# ADF4351.net
KiCad netlist of a schematic drawn in EAGLE
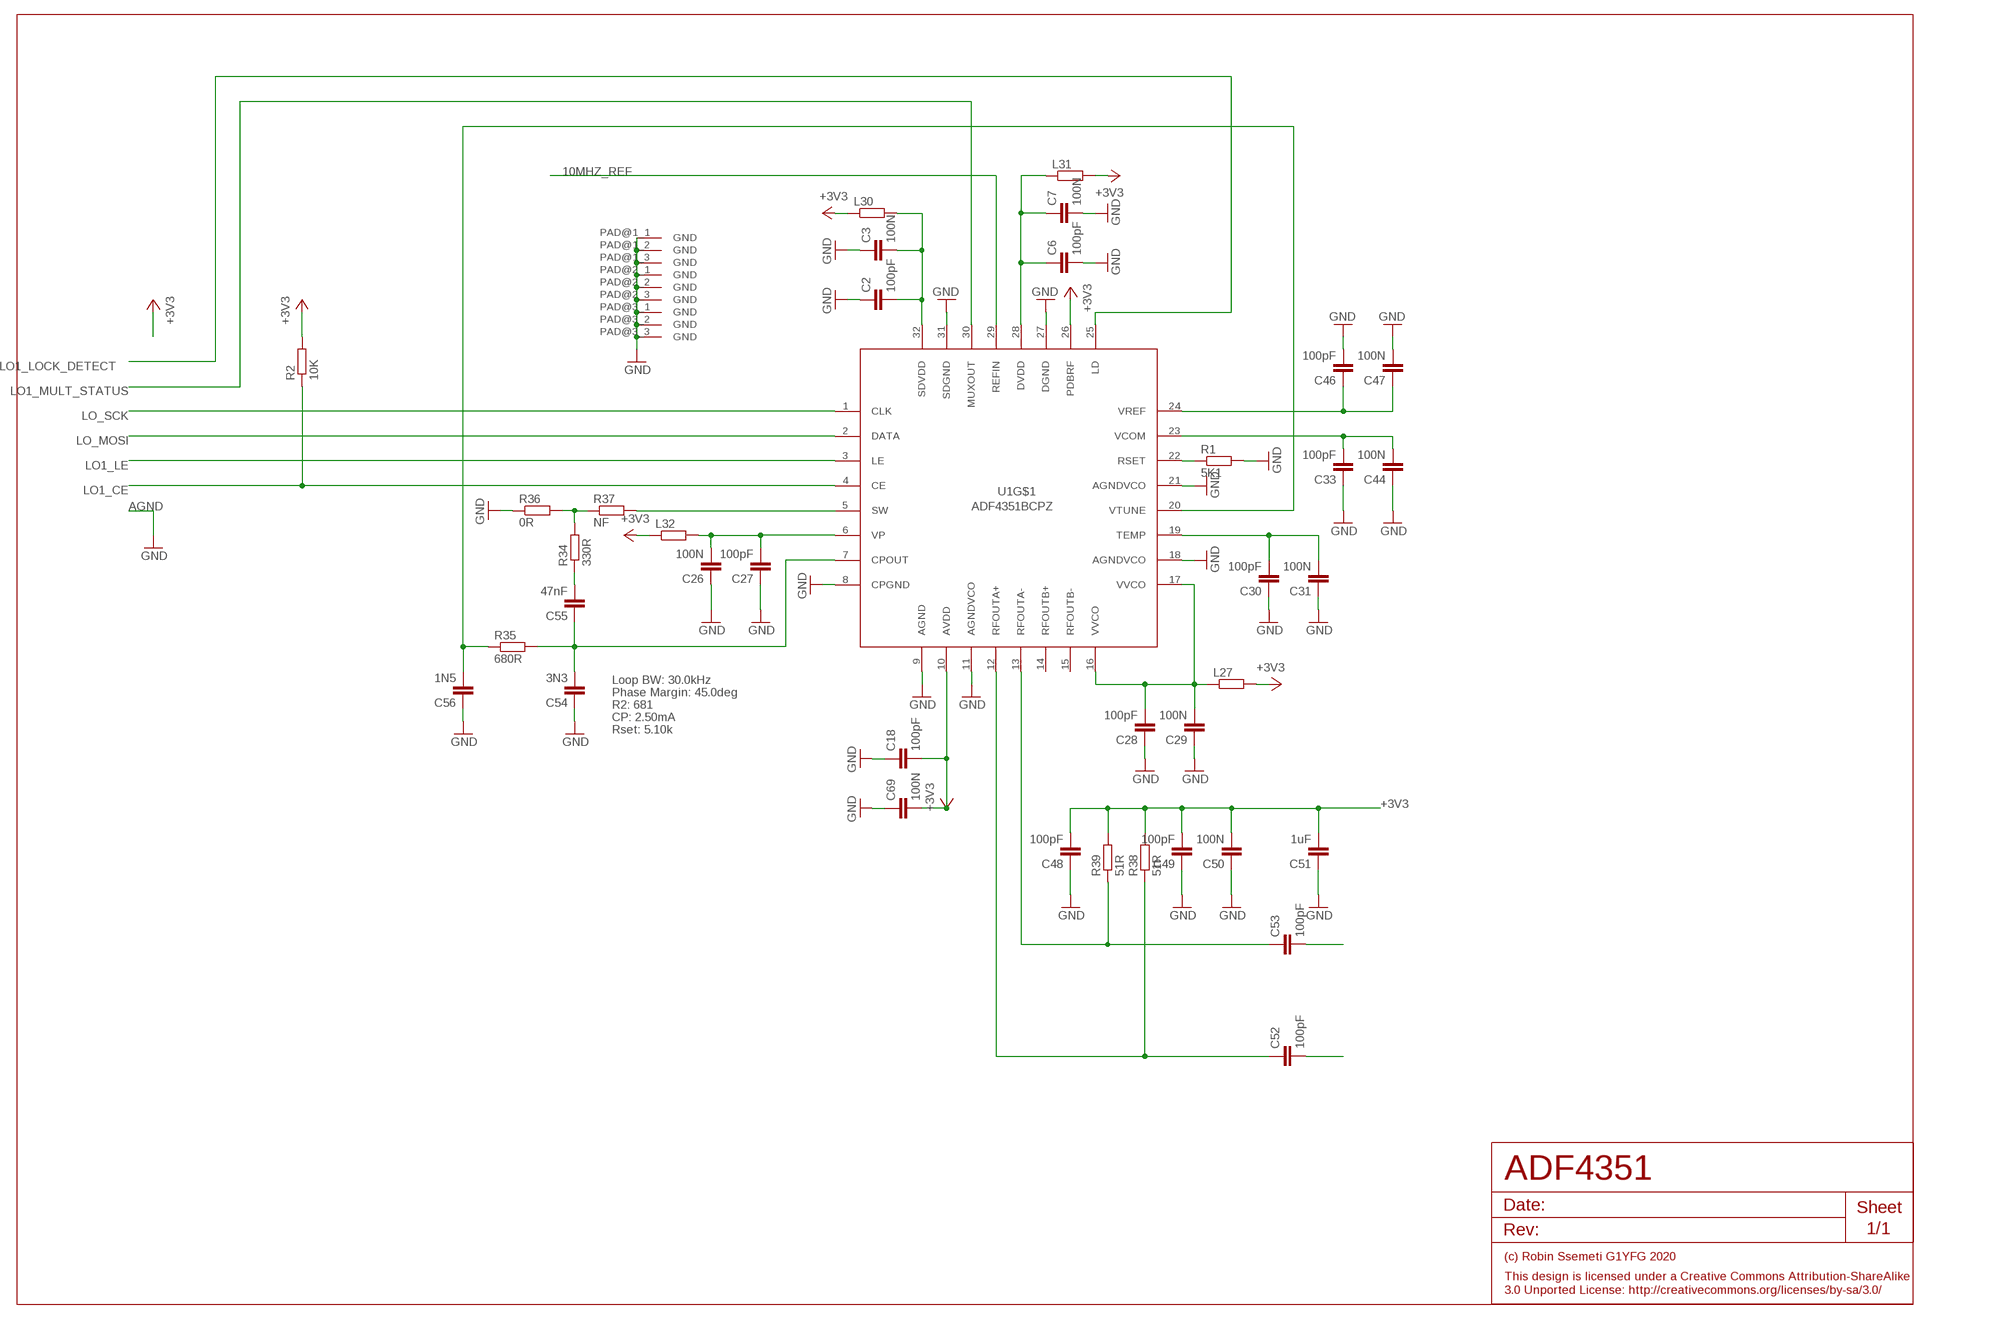
[diagram p0: schematic, sheet 1]

(export (version "E")
  (design (tool "Eeschema 10.0.6"))
  (components
    (comp (ref "C2")
      (value "100pF")
      (footprint "eagle-import:C0603")
      (libsource (lib "eagle-import") (part "C-EUC0603"))
    )
    (comp (ref "C3")
      (value "100N")
      (footprint "eagle-import:C0603")
      (libsource (lib "eagle-import") (part "C-EUC0603"))
    )
    (comp (ref "C6")
      (value "100pF")
      (footprint "eagle-import:C0603")
      (libsource (lib "eagle-import") (part "C-EUC0603"))
    )
    (comp (ref "C7")
      (value "100N")
      (footprint "eagle-import:C0603")
      (libsource (lib "eagle-import") (part "C-EUC0603"))
    )
    (comp (ref "C18")
      (value "100pF")
      (footprint "eagle-import:C0603")
      (libsource (lib "eagle-import") (part "C-EUC0603"))
    )
    (comp (ref "C26")
      (value "100N")
      (footprint "eagle-import:C0603")
      (libsource (lib "eagle-import") (part "C-EUC0603"))
    )
    (comp (ref "C27")
      (value "100pF")
      (footprint "eagle-import:C0603")
      (libsource (lib "eagle-import") (part "C-EUC0603"))
    )
    (comp (ref "C28")
      (value "100pF")
      (footprint "eagle-import:C0603")
      (libsource (lib "eagle-import") (part "C-EUC0603"))
    )
    (comp (ref "C29")
      (value "100N")
      (footprint "eagle-import:C0603")
      (libsource (lib "eagle-import") (part "C-EUC0603"))
    )
    (comp (ref "C30")
      (value "100pF")
      (footprint "eagle-import:C0603")
      (libsource (lib "eagle-import") (part "C-EUC0603"))
    )
    (comp (ref "C31")
      (value "100N")
      (footprint "eagle-import:C0603")
      (libsource (lib "eagle-import") (part "C-EUC0603"))
    )
    (comp (ref "C33")
      (value "100pF")
      (footprint "eagle-import:C0603")
      (libsource (lib "eagle-import") (part "C-EUC0603"))
    )
    (comp (ref "C44")
      (value "100N")
      (footprint "eagle-import:C0603")
      (libsource (lib "eagle-import") (part "C-EUC0603"))
    )
    (comp (ref "C46")
      (value "100pF")
      (footprint "eagle-import:C0603")
      (libsource (lib "eagle-import") (part "C-EUC0603"))
    )
    (comp (ref "C47")
      (value "100N")
      (footprint "eagle-import:C0603")
      (libsource (lib "eagle-import") (part "C-EUC0603"))
    )
    (comp (ref "C48")
      (value "100pF")
      (footprint "eagle-import:C0603")
      (libsource (lib "eagle-import") (part "C-EUC0603"))
    )
    (comp (ref "C49")
      (value "100pF")
      (footprint "eagle-import:C0603")
      (libsource (lib "eagle-import") (part "C-EUC0603"))
    )
    (comp (ref "C50")
      (value "100N")
      (footprint "eagle-import:C0603")
      (libsource (lib "eagle-import") (part "C-EUC0603"))
    )
    (comp (ref "C51")
      (value "1uF")
      (footprint "eagle-import:C0603")
      (libsource (lib "eagle-import") (part "C-EUC0603"))
    )
    (comp (ref "C52")
      (value "100pF")
      (footprint "eagle-import:C0603")
      (libsource (lib "eagle-import") (part "C-EUC0603"))
    )
    (comp (ref "C53")
      (value "100pF")
      (footprint "eagle-import:C0603")
      (libsource (lib "eagle-import") (part "C-EUC0603"))
    )
    (comp (ref "C54")
      (value "3N3")
      (footprint "eagle-import:C0603")
      (libsource (lib "eagle-import") (part "C-EUC0603"))
    )
    (comp (ref "C55")
      (value "47nF")
      (footprint "eagle-import:C0603")
      (libsource (lib "eagle-import") (part "C-EUC0603"))
    )
    (comp (ref "C56")
      (value "1N5")
      (footprint "eagle-import:C0603")
      (libsource (lib "eagle-import") (part "C-EUC0603"))
    )
    (comp (ref "C69")
      (value "100N")
      (footprint "eagle-import:C0603")
      (libsource (lib "eagle-import") (part "C-EUC0603"))
    )
    (comp (ref "L27")
      (value "R-EU_R0603")
      (footprint "eagle-import:R0603")
      (libsource (lib "eagle-import") (part "R-EU_R0603"))
    )
    (comp (ref "L30")
      (value "R-EU_R0603")
      (footprint "eagle-import:R0603")
      (libsource (lib "eagle-import") (part "R-EU_R0603"))
    )
    (comp (ref "L31")
      (value "R-EU_R0603")
      (footprint "eagle-import:R0603")
      (libsource (lib "eagle-import") (part "R-EU_R0603"))
    )
    (comp (ref "L32")
      (value "R-EU_R0603")
      (footprint "eagle-import:R0603")
      (libsource (lib "eagle-import") (part "R-EU_R0603"))
    )
    (comp (ref "R1")
      (value "5K1")
      (footprint "eagle-import:R0603")
      (libsource (lib "eagle-import") (part "R-EU_R0603"))
    )
    (comp (ref "R2")
      (value "10K")
      (footprint "eagle-import:R0603")
      (libsource (lib "eagle-import") (part "resistor_R-EU_R0603"))
    )
    (comp (ref "R34")
      (value "330R")
      (footprint "eagle-import:R0603")
      (libsource (lib "eagle-import") (part "R-EU_R0603"))
    )
    (comp (ref "R35")
      (value "680R")
      (footprint "eagle-import:R0603")
      (libsource (lib "eagle-import") (part "resistor_R-EU_R0603"))
    )
    (comp (ref "R36")
      (value "0R")
      (footprint "eagle-import:R0603")
      (libsource (lib "eagle-import") (part "R-EU_R0603"))
    )
    (comp (ref "R37")
      (value "NF")
      (footprint "eagle-import:R0603")
      (libsource (lib "eagle-import") (part "R-EU_R0603"))
    )
    (comp (ref "R38")
      (value "51R")
      (footprint "eagle-import:R0603")
      (libsource (lib "eagle-import") (part "resistor_R-EU_R0603"))
    )
    (comp (ref "R39")
      (value "51R")
      (footprint "eagle-import:R0603")
      (libsource (lib "eagle-import") (part "resistor_R-EU_R0603"))
    )
    (comp (ref "U1")
      (value "ADF4351BCPZ")
      (footprint "eagle-import:QFN50P500X500X100-33V2N")
      (libsource (lib "eagle-import") (part "ADF4350BCPZ"))
    )
  )
  (nets
    (net (code "1") (name "+3V3") (class "Default")
      (node (ref "C18") (pin "2") (pinfunction "2_2") (pintype "passive"))
      (node (ref "C48") (pin "2") (pinfunction "2_2") (pintype "passive"))
      (node (ref "C49") (pin "2") (pinfunction "2_2") (pintype "passive"))
      (node (ref "C50") (pin "2") (pinfunction "2_2") (pintype "passive"))
      (node (ref "C51") (pin "2") (pinfunction "2_2") (pintype "passive"))
      (node (ref "C69") (pin "2") (pinfunction "2_2") (pintype "passive"))
      (node (ref "L27") (pin "2") (pinfunction "2_2") (pintype "passive"))
      (node (ref "L30") (pin "1") (pinfunction "1_1") (pintype "passive"))
      (node (ref "L31") (pin "2") (pinfunction "2_2") (pintype "passive"))
      (node (ref "L32") (pin "1") (pinfunction "1_1") (pintype "passive"))
      (node (ref "R2") (pin "2") (pinfunction "2_2") (pintype "passive"))
      (node (ref "R38") (pin "2") (pinfunction "2_2") (pintype "passive"))
      (node (ref "R39") (pin "2") (pinfunction "2_2") (pintype "passive"))
      (node (ref "U1") (pin "10") (pinfunction "AVDD_10") (pintype "power_in"))
      (node (ref "U1") (pin "26") (pinfunction "PDBRF_26") (pintype "input"))
    )
    (net (code "2") (name "/10MHZ_REF") (class "Default")
      (node (ref "U1") (pin "29") (pinfunction "REFIN_29") (pintype "input"))
    )
    (net (code "3") (name "/LO1_CE") (class "Default")
      (node (ref "R2") (pin "1") (pinfunction "1_1") (pintype "passive"))
      (node (ref "U1") (pin "4") (pinfunction "CE_4") (pintype "input"))
    )
    (net (code "4") (name "/LO1_LE") (class "Default")
      (node (ref "U1") (pin "3") (pinfunction "LE_3") (pintype "input"))
    )
    (net (code "5") (name "/LO1_LOCK_DETECT") (class "Default")
      (node (ref "U1") (pin "25") (pinfunction "LD_25") (pintype "output"))
    )
    (net (code "6") (name "/LO1_MULT_STATUS") (class "Default")
      (node (ref "U1") (pin "30") (pinfunction "MUXOUT_30") (pintype "output"))
    )
    (net (code "7") (name "/LO_MOSI") (class "Default")
      (node (ref "U1") (pin "2") (pinfunction "DATA_2") (pintype "input"))
    )
    (net (code "8") (name "/LO_SCK") (class "Default")
      (node (ref "U1") (pin "1") (pinfunction "CLK_1") (pintype "input"))
    )
    (net (code "9") (name "GND") (class "Default")
      (node (ref "C18") (pin "1") (pinfunction "1_1") (pintype "passive"))
      (node (ref "C2") (pin "1") (pinfunction "1_1") (pintype "passive"))
      (node (ref "C26") (pin "1") (pinfunction "1_1") (pintype "passive"))
      (node (ref "C27") (pin "1") (pinfunction "1_1") (pintype "passive"))
      (node (ref "C28") (pin "1") (pinfunction "1_1") (pintype "passive"))
      (node (ref "C29") (pin "1") (pinfunction "1_1") (pintype "passive"))
      (node (ref "C3") (pin "1") (pinfunction "1_1") (pintype "passive"))
      (node (ref "C30") (pin "1") (pinfunction "1_1") (pintype "passive"))
      (node (ref "C31") (pin "1") (pinfunction "1_1") (pintype "passive"))
      (node (ref "C33") (pin "1") (pinfunction "1_1") (pintype "passive"))
      (node (ref "C44") (pin "1") (pinfunction "1_1") (pintype "passive"))
      (node (ref "C46") (pin "2") (pinfunction "2_2") (pintype "passive"))
      (node (ref "C47") (pin "2") (pinfunction "2_2") (pintype "passive"))
      (node (ref "C48") (pin "1") (pinfunction "1_1") (pintype "passive"))
      (node (ref "C49") (pin "1") (pinfunction "1_1") (pintype "passive"))
      (node (ref "C50") (pin "1") (pinfunction "1_1") (pintype "passive"))
      (node (ref "C51") (pin "1") (pinfunction "1_1") (pintype "passive"))
      (node (ref "C54") (pin "1") (pinfunction "1_1") (pintype "passive"))
      (node (ref "C56") (pin "1") (pinfunction "1_1") (pintype "passive"))
      (node (ref "C6") (pin "2") (pinfunction "2_2") (pintype "passive"))
      (node (ref "C69") (pin "1") (pinfunction "1_1") (pintype "passive"))
      (node (ref "C7") (pin "2") (pinfunction "2_2") (pintype "passive"))
      (node (ref "R1") (pin "2") (pinfunction "2_2") (pintype "passive"))
      (node (ref "R36") (pin "1") (pinfunction "1_1") (pintype "passive"))
      (node (ref "U1") (pin "11") (pinfunction "AGNDVCO_11") (pintype "power_in"))
      (node (ref "U1") (pin "18") (pinfunction "AGNDVCO_18") (pintype "power_in"))
      (node (ref "U1") (pin "21") (pinfunction "AGNDVCO_21") (pintype "power_in"))
      (node (ref "U1") (pin "27") (pinfunction "DGND_27") (pintype "power_in"))
      (node (ref "U1") (pin "31") (pinfunction "SDGND_31") (pintype "power_in"))
      (node (ref "U1") (pin "8") (pinfunction "CPGND_8") (pintype "power_in"))
      (node (ref "U1") (pin "9") (pinfunction "AGND_9") (pintype "power_in"))
      (node (ref "U1") (pin "PAD@1_1") (pinfunction "GND_PAD@1_1") (pintype "power_in"))
      (node (ref "U1") (pin "PAD@1_2") (pinfunction "GND_PAD@1_2") (pintype "power_in"))
      (node (ref "U1") (pin "PAD@1_3") (pinfunction "GND_PAD@1_3") (pintype "power_in"))
      (node (ref "U1") (pin "PAD@2_1") (pinfunction "GND_PAD@2_1") (pintype "power_in"))
      (node (ref "U1") (pin "PAD@2_2") (pinfunction "GND_PAD@2_2") (pintype "power_in"))
      (node (ref "U1") (pin "PAD@2_3") (pinfunction "GND_PAD@2_3") (pintype "power_in"))
      (node (ref "U1") (pin "PAD@3_1") (pinfunction "GND_PAD@3_1") (pintype "power_in"))
      (node (ref "U1") (pin "PAD@3_2") (pinfunction "GND_PAD@3_2") (pintype "power_in"))
      (node (ref "U1") (pin "PAD@3_3") (pinfunction "GND_PAD@3_3") (pintype "power_in"))
    )
    (net (code "10") (name "Net-(C28-Pad2)") (class "Default")
      (node (ref "C28") (pin "2") (pinfunction "2_2") (pintype "passive"))
      (node (ref "C29") (pin "2") (pinfunction "2_2") (pintype "passive"))
      (node (ref "L27") (pin "1") (pinfunction "1_1") (pintype "passive"))
      (node (ref "U1") (pin "16") (pinfunction "VVCO_16") (pintype "power_in"))
      (node (ref "U1") (pin "17") (pinfunction "VVCO_17") (pintype "power_in"))
    )
    (net (code "11") (name "Net-(C55-Pad2)") (class "Default")
      (node (ref "C55") (pin "2") (pinfunction "2_2") (pintype "passive"))
      (node (ref "R34") (pin "1") (pinfunction "1_1") (pintype "passive"))
    )
    (net (code "12") (name "Net-(R34-Pad2)") (class "Default")
      (node (ref "R34") (pin "2") (pinfunction "2_2") (pintype "passive"))
      (node (ref "R36") (pin "2") (pinfunction "2_2") (pintype "passive"))
      (node (ref "R37") (pin "1") (pinfunction "1_1") (pintype "passive"))
    )
    (net (code "13") (name "Net-(U1A-CPOUT)") (class "Default")
      (node (ref "C54") (pin "2") (pinfunction "2_2") (pintype "passive"))
      (node (ref "C55") (pin "1") (pinfunction "1_1") (pintype "passive"))
      (node (ref "R35") (pin "2") (pinfunction "2_2") (pintype "passive"))
      (node (ref "U1") (pin "7") (pinfunction "CPOUT_7") (pintype "output"))
    )
    (net (code "14") (name "Net-(U1A-DVDD)") (class "Default")
      (node (ref "C6") (pin "1") (pinfunction "1_1") (pintype "passive"))
      (node (ref "C7") (pin "1") (pinfunction "1_1") (pintype "passive"))
      (node (ref "L31") (pin "1") (pinfunction "1_1") (pintype "passive"))
      (node (ref "U1") (pin "28") (pinfunction "DVDD_28") (pintype "power_in"))
    )
    (net (code "15") (name "Net-(U1A-RFOUTA+)") (class "Default")
      (node (ref "C52") (pin "1") (pinfunction "1_1") (pintype "passive"))
      (node (ref "R38") (pin "1") (pinfunction "1_1") (pintype "passive"))
      (node (ref "U1") (pin "12") (pinfunction "RFOUTA+_12") (pintype "output"))
    )
    (net (code "16") (name "Net-(U1A-RFOUTA-)") (class "Default")
      (node (ref "C53") (pin "1") (pinfunction "1_1") (pintype "passive"))
      (node (ref "R39") (pin "1") (pinfunction "1_1") (pintype "passive"))
      (node (ref "U1") (pin "13") (pinfunction "RFOUTA-_13") (pintype "output"))
    )
    (net (code "17") (name "Net-(U1A-RSET)") (class "Default")
      (node (ref "R1") (pin "1") (pinfunction "1_1") (pintype "passive"))
      (node (ref "U1") (pin "22") (pinfunction "RSET_22") (pintype "input"))
    )
    (net (code "18") (name "Net-(U1A-SDVDD)") (class "Default")
      (node (ref "C2") (pin "2") (pinfunction "2_2") (pintype "passive"))
      (node (ref "C3") (pin "2") (pinfunction "2_2") (pintype "passive"))
      (node (ref "L30") (pin "2") (pinfunction "2_2") (pintype "passive"))
      (node (ref "U1") (pin "32") (pinfunction "SDVDD_32") (pintype "power_in"))
    )
    (net (code "19") (name "Net-(U1A-SW)") (class "Default")
      (node (ref "R37") (pin "2") (pinfunction "2_2") (pintype "passive"))
      (node (ref "U1") (pin "5") (pinfunction "SW_5") (pintype "input"))
    )
    (net (code "20") (name "Net-(U1A-TEMP)") (class "Default")
      (node (ref "C30") (pin "2") (pinfunction "2_2") (pintype "passive"))
      (node (ref "C31") (pin "2") (pinfunction "2_2") (pintype "passive"))
      (node (ref "U1") (pin "19") (pinfunction "TEMP_19") (pintype "output"))
    )
    (net (code "21") (name "Net-(U1A-VCOM)") (class "Default")
      (node (ref "C33") (pin "2") (pinfunction "2_2") (pintype "passive"))
      (node (ref "C44") (pin "2") (pinfunction "2_2") (pintype "passive"))
      (node (ref "U1") (pin "23") (pinfunction "VCOM_23") (pintype "output"))
    )
    (net (code "22") (name "Net-(U1A-VP)") (class "Default")
      (node (ref "C26") (pin "2") (pinfunction "2_2") (pintype "passive"))
      (node (ref "C27") (pin "2") (pinfunction "2_2") (pintype "passive"))
      (node (ref "L32") (pin "2") (pinfunction "2_2") (pintype "passive"))
      (node (ref "U1") (pin "6") (pinfunction "VP_6") (pintype "power_in"))
    )
    (net (code "23") (name "Net-(U1A-VREF)") (class "Default")
      (node (ref "C46") (pin "1") (pinfunction "1_1") (pintype "passive"))
      (node (ref "C47") (pin "1") (pinfunction "1_1") (pintype "passive"))
      (node (ref "U1") (pin "24") (pinfunction "VREF_24") (pintype "output"))
    )
    (net (code "24") (name "Net-(U1A-VTUNE)") (class "Default")
      (node (ref "C56") (pin "2") (pinfunction "2_2") (pintype "passive"))
      (node (ref "R35") (pin "1") (pinfunction "1_1") (pintype "passive"))
      (node (ref "U1") (pin "20") (pinfunction "VTUNE_20") (pintype "input"))
    )
    (net (code "25") (name "unconnected-(C52-Pad2)") (class "Default")
      (node (ref "C52") (pin "2") (pinfunction "2_2") (pintype "passive"))
    )
    (net (code "26") (name "unconnected-(C53-Pad2)") (class "Default")
      (node (ref "C53") (pin "2") (pinfunction "2_2") (pintype "passive"))
    )
    (net (code "27") (name "unconnected-(U1A-RFOUTB+-Pad14)") (class "Default")
      (node (ref "U1") (pin "14") (pinfunction "RFOUTB+_14") (pintype "output"))
    )
    (net (code "28") (name "unconnected-(U1A-RFOUTB--Pad15)") (class "Default")
      (node (ref "U1") (pin "15") (pinfunction "RFOUTB-_15") (pintype "output"))
    )
  )
)
